# LAB-ASDM300F.net
KiCad netlist of a schematic drawn in EAGLE
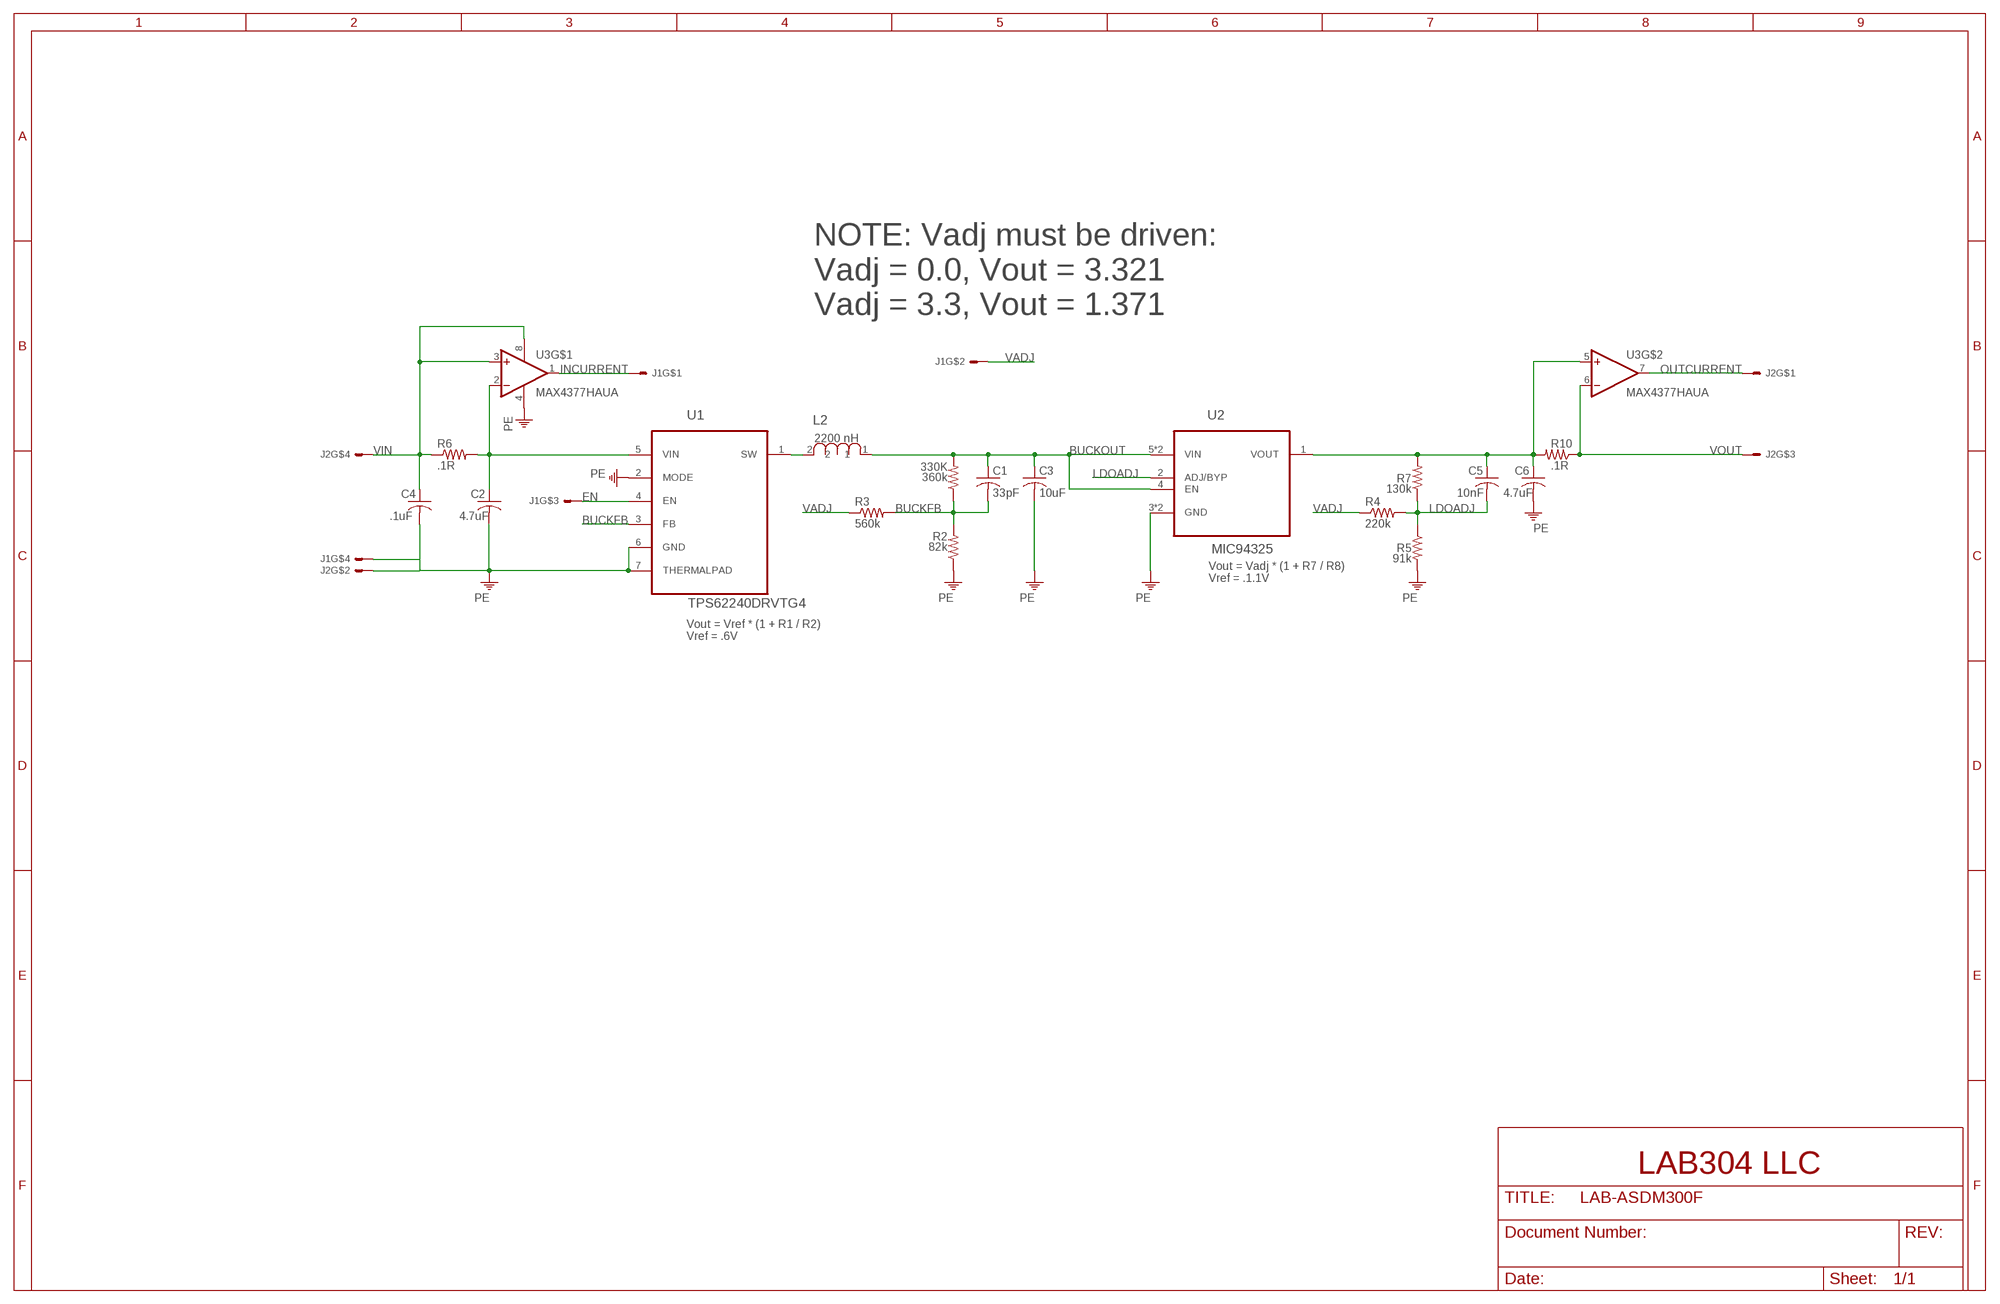
[diagram p0: schematic, sheet 1]

(export (version "E")
  (design (tool "Eeschema 10.0.6"))
  (components
    (comp (ref "330K")
      (value "360k")
      (footprint "eagle-import:R0603")
      (libsource (lib "eagle-import") (part "R-US_R0603"))
    )
    (comp (ref "C1")
      (value "33pF")
      (footprint "eagle-import:C0603")
      (libsource (lib "eagle-import") (part "C-USC0603"))
    )
    (comp (ref "C2")
      (value "4.7uF")
      (footprint "eagle-import:C0603")
      (libsource (lib "eagle-import") (part "C-USC0603"))
    )
    (comp (ref "C3")
      (value "10uF")
      (footprint "eagle-import:C0603")
      (libsource (lib "eagle-import") (part "C-USC0603"))
    )
    (comp (ref "C4")
      (value ".1uF")
      (footprint "eagle-import:C0603")
      (libsource (lib "eagle-import") (part "C-USC0603"))
    )
    (comp (ref "C5")
      (value "10nF")
      (footprint "eagle-import:C0603")
      (libsource (lib "eagle-import") (part "C-USC0603"))
    )
    (comp (ref "C6")
      (value "4.7uF")
      (footprint "eagle-import:C0603")
      (libsource (lib "eagle-import") (part "C-USC0603"))
    )
    (comp (ref "J1")
      (value "SULLINSSMTHEADER-4")
      (footprint "eagle-import:SMTHEADER-4")
      (libsource (lib "eagle-import") (part "SULLINSSMTHEADER-4"))
    )
    (comp (ref "J2")
      (value "SULLINSSMTHEADER-4")
      (footprint "eagle-import:SMTHEADER-4")
      (libsource (lib "eagle-import") (part "SULLINSSMTHEADER-4"))
    )
    (comp (ref "L2")
      (value "2200 nH")
      (footprint "eagle-import:INDC2520X18N")
      (fields (field (name "MPN") "PM1008-2R2K-RC") (field (name "TOLERANCE") "±10 %"))
      (libsource (lib "eagle-import") (part "PM1008-2R2K-RC"))
    )
    (comp (ref "R2")
      (value "82k")
      (footprint "eagle-import:R0603")
      (libsource (lib "eagle-import") (part "R-US_R0603"))
    )
    (comp (ref "R3")
      (value "560k")
      (footprint "eagle-import:R0603")
      (libsource (lib "eagle-import") (part "R-US_R0603"))
    )
    (comp (ref "R4")
      (value "220k")
      (footprint "eagle-import:R0603")
      (libsource (lib "eagle-import") (part "R-US_R0603"))
    )
    (comp (ref "R5")
      (value "91k")
      (footprint "eagle-import:R0603")
      (libsource (lib "eagle-import") (part "R-US_R0603"))
    )
    (comp (ref "R6")
      (value ".1R")
      (footprint "eagle-import:R0603")
      (libsource (lib "eagle-import") (part "R-US_R0603"))
    )
    (comp (ref "R7")
      (value "130k")
      (footprint "eagle-import:R0603")
      (libsource (lib "eagle-import") (part "R-US_R0603"))
    )
    (comp (ref "R10")
      (value ".1R")
      (footprint "eagle-import:R0603")
      (libsource (lib "eagle-import") (part "R-US_R0603"))
    )
    (comp (ref "U1")
      (value "TPS62240DRVTG4")
      (footprint "eagle-import:SON65P210X210X80-7N")
      (libsource (lib "eagle-import") (part "TPS62240DRVTG4"))
    )
    (comp (ref "U2")
      (value "MIC94325")
      (footprint "eagle-import:SON65P160X160X80-7N")
      (libsource (lib "eagle-import") (part "MIC94325"))
    )
    (comp (ref "U3")
      (value "MAX4377HAUA")
      (footprint "eagle-import:UMAX8")
      (libsource (lib "eagle-import") (part "MAX4377"))
    )
  )
  (nets
    (net (code "1") (name "/BUCKFB") (class "Default")
      (node (ref "330K") (pin "1") (pinfunction "1_1") (pintype "passive"))
      (node (ref "C1") (pin "2") (pinfunction "2_2") (pintype "passive"))
      (node (ref "R2") (pin "2") (pinfunction "2_2") (pintype "passive"))
      (node (ref "R3") (pin "2") (pinfunction "2_2") (pintype "passive"))
      (node (ref "U1") (pin "3") (pinfunction "FB_3") (pintype "input"))
    )
    (net (code "2") (name "/BUCKOUT") (class "Default")
      (node (ref "330K") (pin "2") (pinfunction "2_2") (pintype "passive"))
      (node (ref "C1") (pin "1") (pinfunction "1_1") (pintype "passive"))
      (node (ref "C3") (pin "1") (pinfunction "1_1") (pintype "passive"))
      (node (ref "L2") (pin "1") (pinfunction "1_1") (pintype "passive"))
      (node (ref "U2") (pin "4") (pinfunction "EN_4") (pintype "input"))
      (node (ref "U2") (pin "5") (pinfunction "VIN_5") (pintype "power_in"))
      (node (ref "U2") (pin "6") (pinfunction "VIN_6") (pintype "power_in"))
    )
    (net (code "3") (name "/EN") (class "Default")
      (node (ref "J1") (pin "P$3") (pinfunction "S_P$3") (pintype "passive"))
      (node (ref "U1") (pin "4") (pinfunction "EN_4") (pintype "input"))
    )
    (net (code "4") (name "/INCURRENT") (class "Default")
      (node (ref "J1") (pin "P$1") (pinfunction "S_P$1") (pintype "passive"))
      (node (ref "U3") (pin "1") (pinfunction "OUT_1") (pintype "output"))
    )
    (net (code "5") (name "/LDOADJ") (class "Default")
      (node (ref "C5") (pin "2") (pinfunction "2_2") (pintype "passive"))
      (node (ref "R4") (pin "2") (pinfunction "2_2") (pintype "passive"))
      (node (ref "R5") (pin "1") (pinfunction "1_1") (pintype "passive"))
      (node (ref "R7") (pin "1") (pinfunction "1_1") (pintype "passive"))
      (node (ref "U2") (pin "2") (pinfunction "ADJ/BYP_2") (pintype "input"))
    )
    (net (code "6") (name "/OUTCURRENT") (class "Default")
      (node (ref "J2") (pin "P$1") (pinfunction "S_P$1") (pintype "passive"))
      (node (ref "U3") (pin "7") (pinfunction "OUT_7") (pintype "output"))
    )
    (net (code "7") (name "/VADJ") (class "Default")
      (node (ref "J1") (pin "P$2") (pinfunction "S_P$2") (pintype "passive"))
      (node (ref "R3") (pin "1") (pinfunction "1_1") (pintype "passive"))
      (node (ref "R4") (pin "1") (pinfunction "1_1") (pintype "passive"))
    )
    (net (code "8") (name "/VIN") (class "Default")
      (node (ref "C4") (pin "1") (pinfunction "1_1") (pintype "passive"))
      (node (ref "J2") (pin "P$4") (pinfunction "S_P$4") (pintype "passive"))
      (node (ref "R6") (pin "1") (pinfunction "1_1") (pintype "passive"))
      (node (ref "U3") (pin "3") (pinfunction "+IN_3") (pintype "input"))
      (node (ref "U3") (pin "8") (pinfunction "V+_8") (pintype "power_in"))
    )
    (net (code "9") (name "/VOUT") (class "Default")
      (node (ref "J2") (pin "P$3") (pinfunction "S_P$3") (pintype "passive"))
      (node (ref "R10") (pin "1") (pinfunction "1_1") (pintype "passive"))
      (node (ref "U3") (pin "6") (pinfunction "-IN_6") (pintype "input"))
    )
    (net (code "10") (name "Net-(U1-SW)") (class "Default")
      (node (ref "L2") (pin "2") (pinfunction "2_2") (pintype "passive"))
      (node (ref "U1") (pin "1") (pinfunction "SW_1") (pintype "output"))
    )
    (net (code "11") (name "Net-(U1-VIN)") (class "Default")
      (node (ref "C2") (pin "1") (pinfunction "1_1") (pintype "passive"))
      (node (ref "R6") (pin "2") (pinfunction "2_2") (pintype "passive"))
      (node (ref "U1") (pin "5") (pinfunction "VIN_5") (pintype "power_in"))
      (node (ref "U3") (pin "2") (pinfunction "-IN_2") (pintype "input"))
    )
    (net (code "12") (name "Net-(U2-VOUT)") (class "Default")
      (node (ref "C5") (pin "1") (pinfunction "1_1") (pintype "passive"))
      (node (ref "C6") (pin "1") (pinfunction "1_1") (pintype "passive"))
      (node (ref "R10") (pin "2") (pinfunction "2_2") (pintype "passive"))
      (node (ref "R7") (pin "2") (pinfunction "2_2") (pintype "passive"))
      (node (ref "U2") (pin "1") (pinfunction "VOUT_1") (pintype "output"))
      (node (ref "U3") (pin "5") (pinfunction "+IN_5") (pintype "input"))
    )
    (net (code "13") (name "PE") (class "Default")
      (node (ref "C2") (pin "2") (pinfunction "2_2") (pintype "passive"))
      (node (ref "C3") (pin "2") (pinfunction "2_2") (pintype "passive"))
      (node (ref "C4") (pin "2") (pinfunction "2_2") (pintype "passive"))
      (node (ref "C6") (pin "2") (pinfunction "2_2") (pintype "passive"))
      (node (ref "J1") (pin "P$4") (pinfunction "S_P$4") (pintype "passive"))
      (node (ref "J2") (pin "P$2") (pinfunction "S_P$2") (pintype "passive"))
      (node (ref "R2") (pin "1") (pinfunction "1_1") (pintype "passive"))
      (node (ref "R5") (pin "2") (pinfunction "2_2") (pintype "passive"))
      (node (ref "U1") (pin "2") (pinfunction "MODE_2") (pintype "input"))
      (node (ref "U1") (pin "6") (pinfunction "GND_6") (pintype "passive"))
      (node (ref "U1") (pin "7") (pinfunction "THERMALPAD_7") (pintype "passive"))
      (node (ref "U2") (pin "3") (pinfunction "GND_3") (pintype "passive"))
      (node (ref "U2") (pin "7") (pinfunction "GND_7") (pintype "passive"))
      (node (ref "U3") (pin "4") (pinfunction "V-_4") (pintype "power_in"))
    )
  )
)
